# TCAN1146_PINOUT.net
KiCad netlist of a schematic drawn in Altium Designer
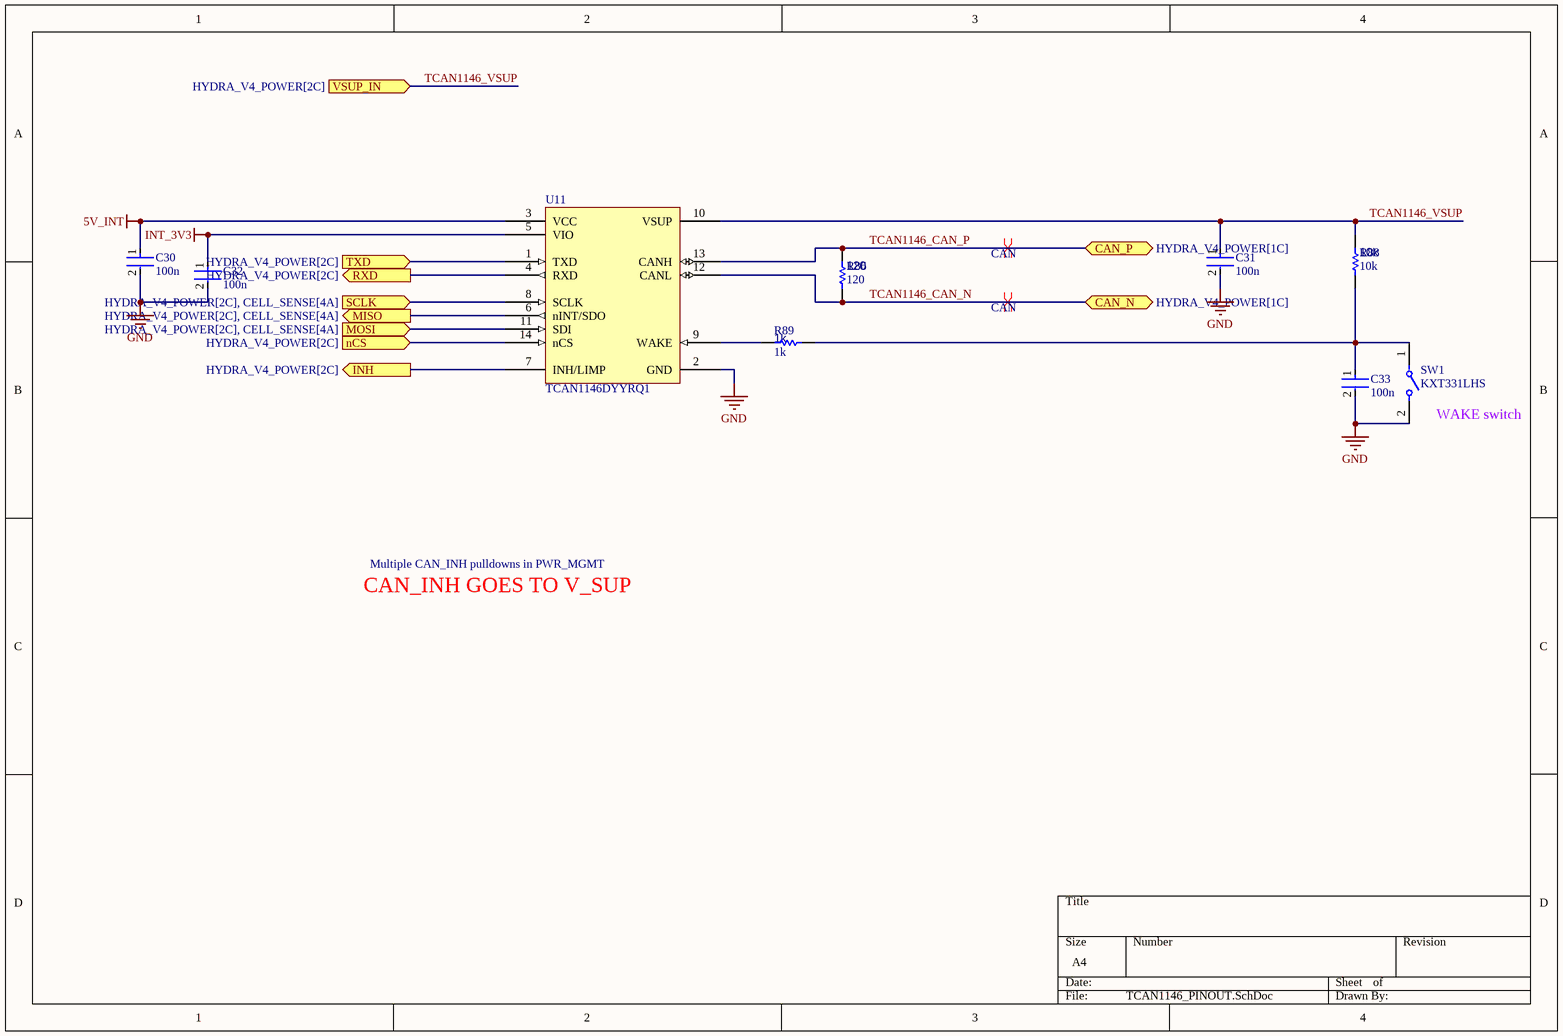
[diagram p0: TCAN1146_PINOUT.SchDoc]

(export (version "E")
  (design (tool "Eeschema 10.0.6"))
  (components
    (comp (ref "C30")
      (value "100n")
      (footprint "FP-0402-L_1_0_0_05-W_0_5-IPC_A")
      (description "LARGE PADS, 0402 CAP, CHANGE COMMENT TO MATCH REAL P/N")
      (libsource (lib "Space Concordia") (part "b4654b650e69147ec39a6b967a45e02"))
    )
    (comp (ref "C31")
      (value "100n")
      (footprint "FP-0402-L_1_0_0_05-W_0_5-IPC_A")
      (description "LARGE PADS, 0402 CAP, CHANGE COMMENT TO MATCH REAL P/N")
      (libsource (lib "Space Concordia") (part "b4654b650e69147ec39a6b967a45e02"))
    )
    (comp (ref "C32")
      (value "100n")
      (footprint "FP-0402-L_1_0_0_05-W_0_5-IPC_A")
      (description "LARGE PADS, 0402 CAP, CHANGE COMMENT TO MATCH REAL P/N")
      (libsource (lib "Space Concordia") (part "b4654b650e69147ec39a6b967a45e02"))
    )
    (comp (ref "C33")
      (value "100n")
      (footprint "FP-0402-L_1_0_0_05-W_0_5-IPC_A")
      (description "LARGE PADS, 0402 CAP, CHANGE COMMENT TO MATCH REAL P/N")
      (libsource (lib "Space Concordia") (part "b4654b650e69147ec39a6b967a45e02"))
    )
    (comp (ref "R86")
      (value "120")
      (footprint "R0603B")
      (description "Resistor")
      (fields (field (name "ALTIUM_VALUE") "120"))
      (libsource (lib "Space Concordia") (part "Resistor"))
    )
    (comp (ref "R88")
      (value "10k")
      (footprint "R0603B")
      (description "Resistor")
      (fields (field (name "ALTIUM_VALUE") "10k"))
      (libsource (lib "Space Concordia") (part "Resistor"))
    )
    (comp (ref "R89")
      (value "1k")
      (footprint "R0603B")
      (description "Resistor")
      (fields (field (name "ALTIUM_VALUE") "1k"))
      (libsource (lib "Space Concordia") (part "Resistor"))
    )
    (comp (ref "SW1")
      (value "KXT331LHS")
      (footprint "FP-KXT331LHS-MFG")
      (description "SWITCH TACTILE SPST-NO 0.02A 15V")
      (libsource (lib "Altium Content Vault") (part "bb27bde45df87f1f469753f287ef5ae"))
    )
    (comp (ref "U11")
      (value "TCAN1146DYYRQ1")
      (footprint "TCAN1146DYYRQ1-Footprint-1")
      (libsource (lib "Space Concordia") (part "CMP-015-00012-2"))
    )
  )
  (nets
    (net (code "1") (name "/INH") (class "Default")
      (node (ref "U11") (pin "7") (pinfunction "INH/LIMP_7") (pintype "passive"))
    )
    (net (code "2") (name "/MISO") (class "Default")
      (node (ref "U11") (pin "6") (pinfunction "nINT/SDO_6") (pintype "output"))
    )
    (net (code "3") (name "/MOSI") (class "Default")
      (node (ref "U11") (pin "11") (pinfunction "SDI_11") (pintype "input"))
    )
    (net (code "4") (name "/RXD") (class "Default")
      (node (ref "U11") (pin "4") (pinfunction "RXD_4") (pintype "output"))
    )
    (net (code "5") (name "/SCLK") (class "Default")
      (node (ref "U11") (pin "8") (pinfunction "SCLK_8") (pintype "input"))
    )
    (net (code "6") (name "/TCAN1146_CAN_N") (class "Default")
      (node (ref "R86") (pin "1") (pinfunction "1_1") (pintype "passive"))
      (node (ref "U11") (pin "12") (pinfunction "CANL_12") (pintype "bidirectional"))
    )
    (net (code "7") (name "/TCAN1146_CAN_P") (class "Default")
      (node (ref "R86") (pin "2") (pinfunction "2_2") (pintype "passive"))
      (node (ref "U11") (pin "13") (pinfunction "CANH_13") (pintype "bidirectional"))
    )
    (net (code "8") (name "/TCAN1146_VSUP") (class "Default")
      (node (ref "C31") (pin "1") (pinfunction "1_1") (pintype "passive"))
      (node (ref "R88") (pin "2") (pinfunction "2_2") (pintype "passive"))
      (node (ref "U11") (pin "10") (pinfunction "VSUP_10") (pintype "power_in"))
    )
    (net (code "9") (name "/TXD") (class "Default")
      (node (ref "U11") (pin "1") (pinfunction "TXD_1") (pintype "input"))
    )
    (net (code "10") (name "/nCS") (class "Default")
      (node (ref "U11") (pin "14") (pinfunction "nCS_14") (pintype "input"))
    )
    (net (code "11") (name "5V_INT") (class "Default")
      (node (ref "C30") (pin "1") (pinfunction "1_1") (pintype "passive"))
      (node (ref "U11") (pin "3") (pinfunction "VCC_3") (pintype "power_in"))
    )
    (net (code "12") (name "GND") (class "Default")
      (node (ref "C30") (pin "2") (pinfunction "2_2") (pintype "passive"))
      (node (ref "C31") (pin "2") (pinfunction "2_2") (pintype "passive"))
      (node (ref "C32") (pin "2") (pinfunction "2_2") (pintype "passive"))
      (node (ref "C33") (pin "2") (pinfunction "2_2") (pintype "passive"))
      (node (ref "SW1") (pin "2") (pinfunction "2_2") (pintype "passive"))
      (node (ref "U11") (pin "2") (pinfunction "GND_2") (pintype "power_in"))
    )
    (net (code "13") (name "INT_3V3") (class "Default")
      (node (ref "C32") (pin "1") (pinfunction "1_1") (pintype "passive"))
      (node (ref "U11") (pin "5") (pinfunction "VIO_5") (pintype "power_in"))
    )
    (net (code "14") (name "Net-(C33-Pad1)") (class "Default")
      (node (ref "C33") (pin "1") (pinfunction "1_1") (pintype "passive"))
      (node (ref "R88") (pin "1") (pinfunction "1_1") (pintype "passive"))
      (node (ref "R89") (pin "1") (pinfunction "1_1") (pintype "passive"))
      (node (ref "SW1") (pin "1") (pinfunction "1_1") (pintype "passive"))
    )
    (net (code "15") (name "Net-(U11-WAKE)") (class "Default")
      (node (ref "R89") (pin "2") (pinfunction "2_2") (pintype "passive"))
      (node (ref "U11") (pin "9") (pinfunction "WAKE_9") (pintype "input"))
    )
  )
)
